# GPS.net
KiCad netlist of a schematic drawn in Altium Designer
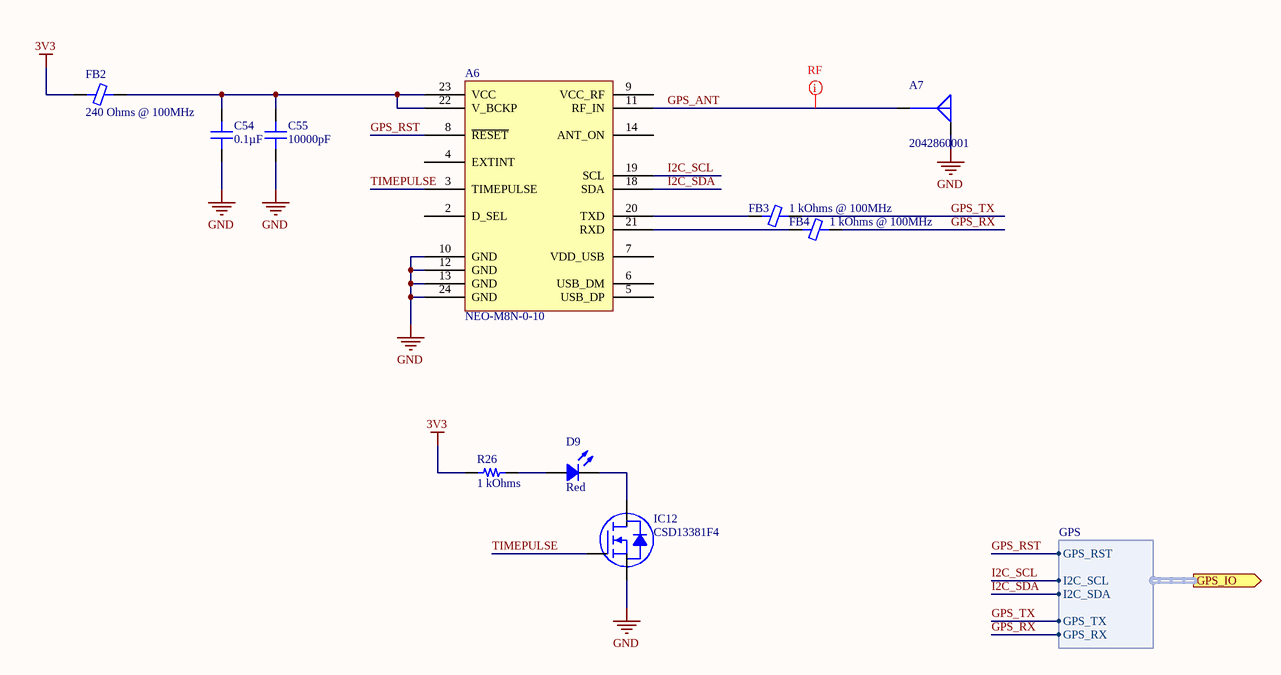
[diagram p0: GPS.SchDoc]

(export (version "E")
  (design (tool "Eeschema 10.0.6"))
  (components
    (comp (ref "A6")
      (value "NEO-M8N-0-10")
      (footprint "U-BLOX NEO-M8N")
      (description "RF RCVR GNSS/GPS 1.575GHZ 24LCC")
      (fields (field (name "MANUFACTURER") "U-Blox America Inc."))
      (libsource (lib "Celestial Altium Library - altium_library") (part "U-BLOX NEO-M8N"))
    )
    (comp (ref "A7")
      (value "2042860001")
      (footprint "MOLEX 2042860001")
      (description "RF ANT CER PATCH SOLDER SMD")
      (fields (field (name "MANUFACTURER") "Molex"))
      (libsource (lib "Celestial Altium Library - altium_library") (part "Basic Antenna"))
    )
    (comp (ref "C54")
      (value "0.1µF")
      (footprint "CAP 0201_0603")
      (description "CAP CER 0.1UF 16V X5R 0201")
      (fields
        (field (name "PART NUMBER") "GRM033R61C104ME84D")
        (field (name "MANUFACTURER") "Murata Electronics")
      )
      (libsource (lib "Celestial Altium Library - altium_library") (part "Capacitor"))
    )
    (comp (ref "C55")
      (value "10000pF")
      (footprint "CAP 0201_0603")
      (description "CAP CER 10000PF 6.3V X7R 0201")
      (fields
        (field (name "PART NUMBER") "CGA1A2X7R0J103M030BA")
        (field (name "MANUFACTURER") "TDK Corporation")
      )
      (libsource (lib "Celestial Altium Library - altium_library") (part "Capacitor"))
    )
    (comp (ref "D9")
      (value "Red")
      (footprint "LED 0402_1005 RED")
      (description "LED RED CLEAR 0402 SMD")
      (fields (field (name "PART NUMBER") "IN-S42ATR") (field (name "MANUFACTURER") "Inolux"))
      (libsource (lib "Celestial Altium Library - altium_library") (part "LED"))
    )
    (comp (ref "FB2")
      (value "240 Ohms @ 100MHz")
      (footprint "FER 0201_0603")
      (description "FERRITE BEAD 240 OHM 0201 1LN")
      (fields (field (name "PART NUMBER") "BK0603TS241-T") (field (name "MANUFACTURER") "Taiyo Yuden"))
      (libsource (lib "Celestial Altium Library - altium_library") (part "Ferrite Chip"))
    )
    (comp (ref "FB3")
      (value "1 kOhms @ 100MHz")
      (footprint "FER 0201_0603")
      (description "FERRITE BEAD 1 KOHM 0201 1LN")
      (fields (field (name "PART NUMBER") "BK0603HR102-T") (field (name "MANUFACTURER") "Taiyo Yuden"))
      (libsource (lib "Celestial Altium Library - altium_library") (part "Ferrite Chip"))
    )
    (comp (ref "FB4")
      (value "1 kOhms @ 100MHz")
      (footprint "FER 0201_0603")
      (description "FERRITE BEAD 1 KOHM 0201 1LN")
      (fields (field (name "PART NUMBER") "BK0603HR102-T") (field (name "MANUFACTURER") "Taiyo Yuden"))
      (libsource (lib "Celestial Altium Library - altium_library") (part "Ferrite Chip"))
    )
    (comp (ref "IC12")
      (value "CSD13381F4")
      (footprint "TI 3-XFDFN F4 YJC")
      (description "MOSFET N-CH 12V 2.1A 3PICOSTAR")
      (fields (field (name "MANUFACTURER") "Texas Instruments"))
      (libsource (lib "Celestial Altium Library - altium_library") (part "TI CSD MOSFET N-CH F4"))
    )
    (comp (ref "R26")
      (value "1 kOhms")
      (footprint "RES 0201_0603")
      (description "RES SMD 1K OHM 1% 1/20W 0201")
      (fields
        (field (name "PART NUMBER") "ERJ-1GNF1001C")
        (field (name "MANUFACTURER") "Panasonic Electronic Components")
      )
      (libsource (lib "Celestial Altium Library - altium_library") (part "Resistor"))
    )
  )
  (nets
    (net (code "2") (name "/GPS_ANT") (class "Default")
      (node (ref "A6") (pin "11") (pinfunction "RF_IN_11") (pintype "passive"))
      (node (ref "A7") (pin "S") (pinfunction "S_S") (pintype "passive"))
    )
    (net (code "3") (name "/GPS_RST") (class "Default")
      (node (ref "A6") (pin "8") (pinfunction "~{RESET}_8") (pintype "passive"))
    )
    (net (code "4") (name "/GPS_RX") (class "Default")
      (node (ref "FB4") (pin "2") (pinfunction "2_2") (pintype "passive"))
    )
    (net (code "5") (name "/GPS_TX") (class "Default")
      (node (ref "FB3") (pin "2") (pinfunction "2_2") (pintype "passive"))
    )
    (net (code "6") (name "/I2C_SCL") (class "Default")
      (node (ref "A6") (pin "19") (pinfunction "SCL_19") (pintype "passive"))
    )
    (net (code "7") (name "/I2C_SDA") (class "Default")
      (node (ref "A6") (pin "18") (pinfunction "SDA_18") (pintype "passive"))
    )
    (net (code "8") (name "/TIMEPULSE") (class "Default")
      (node (ref "A6") (pin "3") (pinfunction "TIMEPULSE_3") (pintype "passive"))
      (node (ref "IC12") (pin "G") (pinfunction "G_G") (pintype "passive"))
    )
    (net (code "10") (name "3V3") (class "Default")
      (node (ref "FB2") (pin "1") (pinfunction "1_1") (pintype "passive"))
      (node (ref "R26") (pin "1") (pinfunction "1_1") (pintype "passive"))
    )
    (net (code "11") (name "GND") (class "Default")
      (node (ref "A6") (pin "10") (pinfunction "GND_10") (pintype "passive"))
      (node (ref "A6") (pin "12") (pinfunction "GND_12") (pintype "passive"))
      (node (ref "A6") (pin "13") (pinfunction "GND_13") (pintype "passive"))
      (node (ref "A6") (pin "24") (pinfunction "GND_24") (pintype "passive"))
      (node (ref "A7") (pin "G") (pinfunction "G_G") (pintype "passive"))
      (node (ref "C54") (pin "1") (pinfunction "1_1") (pintype "passive"))
      (node (ref "C55") (pin "1") (pinfunction "1_1") (pintype "passive"))
      (node (ref "IC12") (pin "S") (pinfunction "S_S") (pintype "passive"))
    )
    (net (code "12") (name "Net-(A6-RXD)") (class "Default")
      (node (ref "A6") (pin "21") (pinfunction "RXD_21") (pintype "passive"))
      (node (ref "FB4") (pin "1") (pinfunction "1_1") (pintype "passive"))
    )
    (net (code "13") (name "Net-(A6-TXD)") (class "Default")
      (node (ref "A6") (pin "20") (pinfunction "TXD_20") (pintype "passive"))
      (node (ref "FB3") (pin "1") (pinfunction "1_1") (pintype "passive"))
    )
    (net (code "14") (name "Net-(A6-VCC)") (class "Default")
      (node (ref "A6") (pin "22") (pinfunction "V_BCKP_22") (pintype "passive"))
      (node (ref "A6") (pin "23") (pinfunction "VCC_23") (pintype "passive"))
      (node (ref "C54") (pin "2") (pinfunction "2_2") (pintype "passive"))
      (node (ref "C55") (pin "2") (pinfunction "2_2") (pintype "passive"))
      (node (ref "FB2") (pin "2") (pinfunction "2_2") (pintype "passive"))
    )
    (net (code "15") (name "Net-(D9-Pad1)") (class "Default")
      (node (ref "D9") (pin "1") (pinfunction "1_1") (pintype "passive"))
      (node (ref "R26") (pin "2") (pinfunction "2_2") (pintype "passive"))
    )
    (net (code "16") (name "Net-(D9-Pad2)") (class "Default")
      (node (ref "D9") (pin "2") (pinfunction "2_2") (pintype "passive"))
      (node (ref "IC12") (pin "D") (pinfunction "D_D") (pintype "passive"))
    )
    (net (code "17") (name "unconnected-(A6-ANT_ON-Pad14)") (class "Default")
      (node (ref "A6") (pin "14") (pinfunction "ANT_ON_14") (pintype "passive"))
    )
    (net (code "18") (name "unconnected-(A6-D_SEL-Pad2)") (class "Default")
      (node (ref "A6") (pin "2") (pinfunction "D_SEL_2") (pintype "passive"))
    )
    (net (code "19") (name "unconnected-(A6-EXTINT-Pad4)") (class "Default")
      (node (ref "A6") (pin "4") (pinfunction "EXTINT_4") (pintype "passive"))
    )
    (net (code "20") (name "unconnected-(A6-USB_DM-Pad6)") (class "Default")
      (node (ref "A6") (pin "6") (pinfunction "USB_DM_6") (pintype "passive"))
    )
    (net (code "21") (name "unconnected-(A6-USB_DP-Pad5)") (class "Default")
      (node (ref "A6") (pin "5") (pinfunction "USB_DP_5") (pintype "passive"))
    )
    (net (code "22") (name "unconnected-(A6-VCC_RF-Pad9)") (class "Default")
      (node (ref "A6") (pin "9") (pinfunction "VCC_RF_9") (pintype "passive"))
    )
    (net (code "23") (name "unconnected-(A6-VDD_USB-Pad7)") (class "Default")
      (node (ref "A6") (pin "7") (pinfunction "VDD_USB_7") (pintype "passive"))
    )
  )
)
